# MainPower.net
KiCad netlist of a schematic drawn in EAGLE
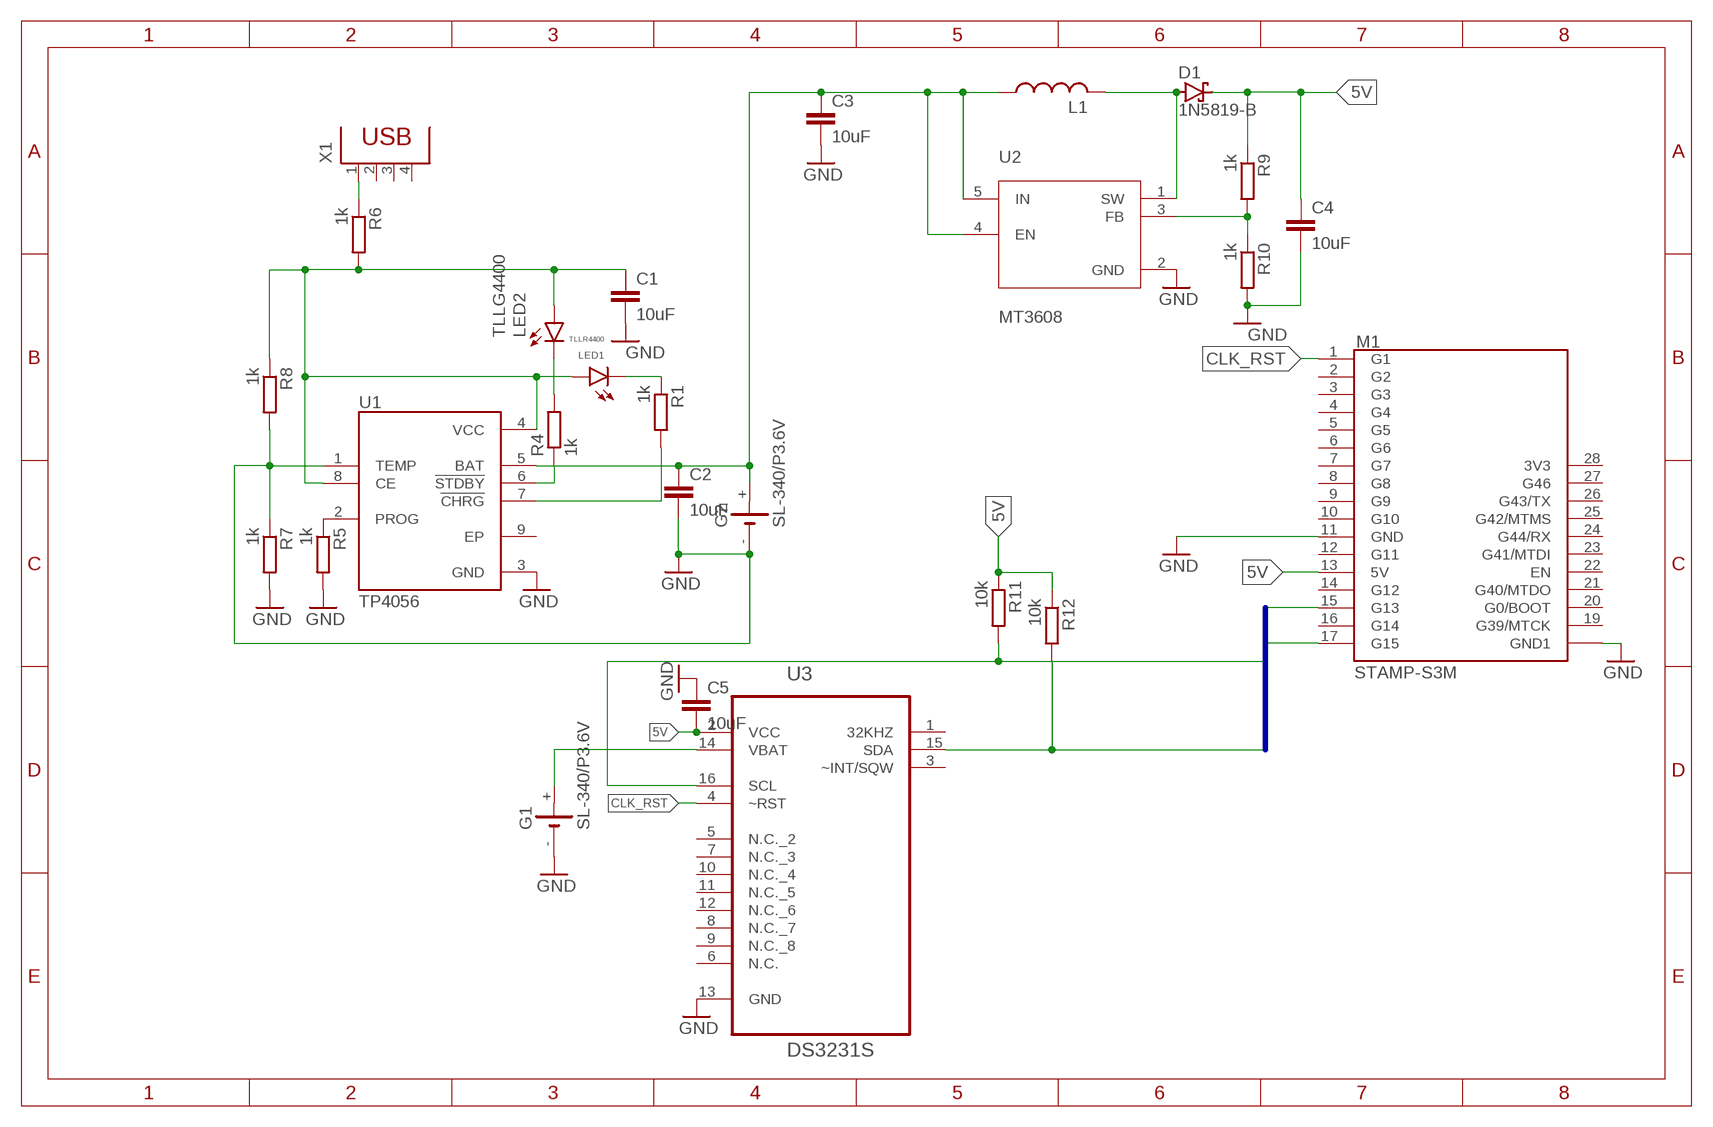
[diagram p0: schematic, sheet 1]

(export (version "E")
  (design (tool "Eeschema 10.0.6"))
  (components
    (comp (ref "C1")
      (value "10uF")
      (footprint "eagle-import:C2.5-3")
      (libsource (lib "eagle-import") (part "C2,5-3"))
    )
    (comp (ref "C2")
      (value "10uF")
      (footprint "eagle-import:C2.5-3")
      (libsource (lib "eagle-import") (part "C2,5-3"))
    )
    (comp (ref "C3")
      (value "10uF")
      (footprint "eagle-import:C2.5-3")
      (libsource (lib "eagle-import") (part "C2,5-3"))
    )
    (comp (ref "C4")
      (value "10uF")
      (footprint "eagle-import:C2.5-3")
      (libsource (lib "eagle-import") (part "C2,5-3"))
    )
    (comp (ref "C5")
      (value "10uF")
      (footprint "eagle-import:C2.5-3")
      (libsource (lib "eagle-import") (part "C2,5-3"))
    )
    (comp (ref "D1")
      (value "1N5819-B")
      (footprint "eagle-import:DO41-7.6")
      (libsource (lib "eagle-import") (part "1N5819-B"))
    )
    (comp (ref "G1")
      (value "SL-340/P3.6V")
      (footprint "eagle-import:SL-340_P3.6V")
      (libsource (lib "eagle-import") (part "SL-340/P3.6V"))
    )
    (comp (ref "G2")
      (value "SL-340/P3.6V")
      (footprint "eagle-import:SL-340_P3.6V")
      (libsource (lib "eagle-import") (part "SL-340/P3.6V"))
    )
    (comp (ref "L1")
      (value "L-US0204/7")
      (footprint "eagle-import:0204_7")
      (libsource (lib "eagle-import") (part "L-US0204/7"))
    )
    (comp (ref "LED1")
      (value "TLLR4400")
      (footprint "eagle-import:LED3MM")
      (fields (field (name "MF") "VISHAY SEMICONDUCTOR"))
      (libsource (lib "eagle-import") (part "TLLR4400"))
    )
    (comp (ref "LED2")
      (value "TLLG4400")
      (footprint "eagle-import:LED3MM")
      (fields (field (name "MF") "VISHAY SEMICONDUCTOR"))
      (libsource (lib "eagle-import") (part "TLLG4400"))
    )
    (comp (ref "R1")
      (value "1k")
      (footprint "eagle-import:0204V")
      (libsource (lib "eagle-import") (part "R-EU_0204/2V"))
    )
    (comp (ref "R4")
      (value "1k")
      (footprint "eagle-import:0204V")
      (libsource (lib "eagle-import") (part "R-EU_0204/2V"))
    )
    (comp (ref "R5")
      (value "1k")
      (footprint "eagle-import:0204V")
      (libsource (lib "eagle-import") (part "R-EU_0204/2V"))
    )
    (comp (ref "R6")
      (value "1k")
      (footprint "eagle-import:0204V")
      (libsource (lib "eagle-import") (part "R-EU_0204/2V"))
    )
    (comp (ref "R7")
      (value "1k")
      (footprint "eagle-import:0204V")
      (libsource (lib "eagle-import") (part "R-EU_0204/2V"))
    )
    (comp (ref "R8")
      (value "1k")
      (footprint "eagle-import:0204V")
      (libsource (lib "eagle-import") (part "R-EU_0204/2V"))
    )
    (comp (ref "R9")
      (value "1k")
      (footprint "eagle-import:0204V")
      (libsource (lib "eagle-import") (part "R-EU_0204/2V"))
    )
    (comp (ref "R10")
      (value "1k")
      (footprint "eagle-import:0204V")
      (libsource (lib "eagle-import") (part "R-EU_0204/2V"))
    )
    (comp (ref "R11")
      (value "10k")
      (footprint "eagle-import:0204V")
      (libsource (lib "eagle-import") (part "R-EU_0204/2V"))
    )
    (comp (ref "R12")
      (value "10k")
      (footprint "eagle-import:0204V")
      (libsource (lib "eagle-import") (part "R-EU_0204/2V"))
    )
    (comp (ref "U$2")
      (value "STAMP-S3M-PIN")
      (footprint "eagle-import:STAMPS3_PIN_FTP")
      (libsource (lib "eagle-import") (part "STAMP-S3M-PIN"))
    )
    (comp (ref "U1")
      (value "TP4056")
      (footprint "eagle-import:SOP127P600X175-9N")
      (fields (field (name "MF") "NanJing Top Power ASIC Corp."))
      (libsource (lib "eagle-import") (part "TP4056"))
    )
    (comp (ref "U2")
      (value "MT3608")
      (footprint "eagle-import:SOT95P280X145-6N")
      (fields (field (name "MF") "Aerosemi Technology Co., Ltd"))
      (libsource (lib "eagle-import") (part "MT3608"))
    )
    (comp (ref "U3")
      (value "DS3231S")
      (footprint "eagle-import:SOIC127P1032X265-16N")
      (fields (field (name "MF") "Analog Devices") (field (name "MP") "DS3231S#"))
      (libsource (lib "eagle-import") (part "DS3231S"))
    )
    (comp (ref "X1")
      (value "PN61729")
      (footprint "eagle-import:PN61729")
      (libsource (lib "eagle-import") (part "PN61729"))
    )
  )
  (nets
    (net (code "1") (name "/3V3") (class "Default")
      (node (ref "U$2") (pin "28") (pinfunction "3V3_28") (pintype "power_in"))
    )
    (net (code "2") (name "/SCL") (class "Default")
      (node (ref "R11") (pin "2") (pinfunction "2_2") (pintype "passive"))
      (node (ref "U$2") (pin "17") (pinfunction "G15_17") (pintype "bidirectional"))
      (node (ref "U3") (pin "16") (pinfunction "SCL_16") (pintype "input"))
    )
    (net (code "3") (name "/SDA") (class "Default")
      (node (ref "R12") (pin "2") (pinfunction "2_2") (pintype "passive"))
      (node (ref "U$2") (pin "15") (pinfunction "G13_15") (pintype "bidirectional"))
      (node (ref "U3") (pin "15") (pinfunction "SDA_15") (pintype "bidirectional"))
    )
    (net (code "4") (name "/USB") (class "Default")
      (node (ref "C1") (pin "1") (pinfunction "1_1") (pintype "passive"))
      (node (ref "LED1") (pin "A") (pinfunction "A_A") (pintype "passive"))
      (node (ref "LED2") (pin "A") (pinfunction "A_A") (pintype "passive"))
      (node (ref "R6") (pin "1") (pinfunction "1_1") (pintype "passive"))
      (node (ref "R6") (pin "2") (pinfunction "2_2") (pintype "passive"))
      (node (ref "R8") (pin "1") (pinfunction "1_1") (pintype "passive"))
      (node (ref "U1") (pin "4") (pinfunction "VCC_4") (pintype "power_in"))
      (node (ref "U1") (pin "8") (pinfunction "CE_8") (pintype "input"))
      (node (ref "X1") (pin "1") (pinfunction "1_1") (pintype "passive"))
    )
    (net (code "5") (name "5V") (class "Default")
      (node (ref "C4") (pin "1") (pinfunction "1_1") (pintype "passive"))
      (node (ref "C5") (pin "2") (pinfunction "2_2") (pintype "passive"))
      (node (ref "D1") (pin "C") (pinfunction "C_C") (pintype "passive"))
      (node (ref "R11") (pin "1") (pinfunction "1_1") (pintype "passive"))
      (node (ref "R12") (pin "1") (pinfunction "1_1") (pintype "passive"))
      (node (ref "R9") (pin "1") (pinfunction "1_1") (pintype "passive"))
      (node (ref "U$2") (pin "13") (pinfunction "5V_13") (pintype "power_in"))
      (node (ref "U3") (pin "2") (pinfunction "VCC_2") (pintype "power_in"))
    )
    (net (code "6") (name "CLK_RST") (class "Default")
      (node (ref "U$2") (pin "1") (pinfunction "G1_1") (pintype "bidirectional"))
      (node (ref "U3") (pin "4") (pinfunction "~{RST}_4") (pintype "bidirectional"))
    )
    (net (code "7") (name "GND") (class "Default")
      (node (ref "C1") (pin "2") (pinfunction "2_2") (pintype "passive"))
      (node (ref "C2") (pin "2") (pinfunction "2_2") (pintype "passive"))
      (node (ref "C3") (pin "2") (pinfunction "2_2") (pintype "passive"))
      (node (ref "C4") (pin "2") (pinfunction "2_2") (pintype "passive"))
      (node (ref "C5") (pin "1") (pinfunction "1_1") (pintype "passive"))
      (node (ref "G1") (pin "-") (pinfunction "-_-") (pintype "passive"))
      (node (ref "G2") (pin "-") (pinfunction "-_-") (pintype "passive"))
      (node (ref "R10") (pin "2") (pinfunction "2_2") (pintype "passive"))
      (node (ref "R5") (pin "2") (pinfunction "2_2") (pintype "passive"))
      (node (ref "R7") (pin "1") (pinfunction "1_1") (pintype "passive"))
      (node (ref "R7") (pin "2") (pinfunction "2_2") (pintype "passive"))
      (node (ref "R8") (pin "2") (pinfunction "2_2") (pintype "passive"))
      (node (ref "U$2") (pin "11") (pinfunction "GND_11") (pintype "power_in"))
      (node (ref "U$2") (pin "18") (pinfunction "GND1_18") (pintype "power_in"))
      (node (ref "U1") (pin "1") (pinfunction "TEMP_1") (pintype "input"))
      (node (ref "U1") (pin "3") (pinfunction "GND_3") (pintype "power_in"))
      (node (ref "U2") (pin "2") (pinfunction "GND_2") (pintype "power_in"))
      (node (ref "U3") (pin "13") (pinfunction "GND_13") (pintype "passive"))
    )
    (net (code "8") (name "Net-(LED1-C)") (class "Default")
      (node (ref "LED1") (pin "K") (pinfunction "C_K") (pintype "passive"))
      (node (ref "R1") (pin "1") (pinfunction "1_1") (pintype "passive"))
    )
    (net (code "9") (name "Net-(LED2-C)") (class "Default")
      (node (ref "LED2") (pin "K") (pinfunction "C_K") (pintype "passive"))
      (node (ref "R4") (pin "2") (pinfunction "2_2") (pintype "passive"))
    )
    (net (code "10") (name "Net-(U1-BAT)") (class "Default")
      (node (ref "C2") (pin "1") (pinfunction "1_1") (pintype "passive"))
      (node (ref "C3") (pin "1") (pinfunction "1_1") (pintype "passive"))
      (node (ref "G2") (pin "+") (pinfunction "+_+") (pintype "passive"))
      (node (ref "L1") (pin "1") (pinfunction "1_1") (pintype "passive"))
      (node (ref "U1") (pin "5") (pinfunction "BAT_5") (pintype "output"))
      (node (ref "U2") (pin "4") (pinfunction "EN_4") (pintype "input"))
      (node (ref "U2") (pin "5") (pinfunction "IN_5") (pintype "input"))
    )
    (net (code "11") (name "Net-(U1-PROG)") (class "Default")
      (node (ref "R5") (pin "1") (pinfunction "1_1") (pintype "passive"))
      (node (ref "U1") (pin "2") (pinfunction "PROG_2") (pintype "bidirectional"))
    )
    (net (code "12") (name "Net-(U1-~{CHRG})") (class "Default")
      (node (ref "R1") (pin "2") (pinfunction "2_2") (pintype "passive"))
      (node (ref "U1") (pin "7") (pinfunction "~{CHRG}_7") (pintype "output"))
    )
    (net (code "13") (name "Net-(U1-~{STDBY})") (class "Default")
      (node (ref "R4") (pin "1") (pinfunction "1_1") (pintype "passive"))
      (node (ref "U1") (pin "6") (pinfunction "~{STDBY}_6") (pintype "output"))
    )
    (net (code "14") (name "Net-(U2-FB)") (class "Default")
      (node (ref "R10") (pin "1") (pinfunction "1_1") (pintype "passive"))
      (node (ref "R9") (pin "2") (pinfunction "2_2") (pintype "passive"))
      (node (ref "U2") (pin "3") (pinfunction "FB_3") (pintype "input"))
    )
    (net (code "15") (name "Net-(U2-SW)") (class "Default")
      (node (ref "D1") (pin "A") (pinfunction "A_A") (pintype "passive"))
      (node (ref "L1") (pin "2") (pinfunction "2_2") (pintype "passive"))
      (node (ref "U2") (pin "1") (pinfunction "SW_1") (pintype "output"))
    )
    (net (code "16") (name "Net-(U3-VBAT)") (class "Default")
      (node (ref "G1") (pin "+") (pinfunction "+_+") (pintype "passive"))
      (node (ref "U3") (pin "14") (pinfunction "VBAT_14") (pintype "power_in"))
    )
    (net (code "17") (name "unconnected-(U$2-EN-Pad22)") (class "Default")
      (node (ref "U$2") (pin "22") (pinfunction "EN_22") (pintype "input"))
    )
    (net (code "18") (name "unconnected-(U$2-G0{slash}BOOT-Pad20)") (class "Default")
      (node (ref "U$2") (pin "20") (pinfunction "G0/BOOT_20") (pintype "bidirectional"))
    )
    (net (code "19") (name "unconnected-(U$2-G2-Pad2)") (class "Default")
      (node (ref "U$2") (pin "2") (pinfunction "G2_2") (pintype "bidirectional"))
    )
    (net (code "20") (name "unconnected-(U$2-G3-Pad3)") (class "Default")
      (node (ref "U$2") (pin "3") (pinfunction "G3_3") (pintype "bidirectional"))
    )
    (net (code "21") (name "unconnected-(U$2-G4-Pad4)") (class "Default")
      (node (ref "U$2") (pin "4") (pinfunction "G4_4") (pintype "bidirectional"))
    )
    (net (code "22") (name "unconnected-(U$2-G5-Pad5)") (class "Default")
      (node (ref "U$2") (pin "5") (pinfunction "G5_5") (pintype "bidirectional"))
    )
    (net (code "23") (name "unconnected-(U$2-G6-Pad6)") (class "Default")
      (node (ref "U$2") (pin "6") (pinfunction "G6_6") (pintype "bidirectional"))
    )
    (net (code "24") (name "unconnected-(U$2-G7-Pad7)") (class "Default")
      (node (ref "U$2") (pin "7") (pinfunction "G7_7") (pintype "bidirectional"))
    )
    (net (code "25") (name "unconnected-(U$2-G8-Pad8)") (class "Default")
      (node (ref "U$2") (pin "8") (pinfunction "G8_8") (pintype "bidirectional"))
    )
    (net (code "26") (name "unconnected-(U$2-G9-Pad9)") (class "Default")
      (node (ref "U$2") (pin "9") (pinfunction "G9_9") (pintype "bidirectional"))
    )
    (net (code "27") (name "unconnected-(U$2-G10-Pad10)") (class "Default")
      (node (ref "U$2") (pin "10") (pinfunction "G10_10") (pintype "bidirectional"))
    )
    (net (code "28") (name "unconnected-(U$2-G11-Pad12)") (class "Default")
      (node (ref "U$2") (pin "12") (pinfunction "G11_12") (pintype "bidirectional"))
    )
    (net (code "29") (name "unconnected-(U$2-G12-Pad14)") (class "Default")
      (node (ref "U$2") (pin "14") (pinfunction "G12_14") (pintype "bidirectional"))
    )
    (net (code "30") (name "unconnected-(U$2-G14-Pad16)") (class "Default")
      (node (ref "U$2") (pin "16") (pinfunction "G14_16") (pintype "bidirectional"))
    )
    (net (code "31") (name "unconnected-(U$2-G39{slash}MTCK-Pad19)") (class "Default")
      (node (ref "U$2") (pin "19") (pinfunction "G39/MTCK_19") (pintype "bidirectional"))
    )
    (net (code "32") (name "unconnected-(U$2-G40{slash}MTDO-Pad21)") (class "Default")
      (node (ref "U$2") (pin "21") (pinfunction "G40/MTDO_21") (pintype "bidirectional"))
    )
    (net (code "33") (name "unconnected-(U$2-G41{slash}MTDI-Pad23)") (class "Default")
      (node (ref "U$2") (pin "23") (pinfunction "G41/MTDI_23") (pintype "bidirectional"))
    )
    (net (code "34") (name "unconnected-(U$2-G42{slash}MTMS-Pad25)") (class "Default")
      (node (ref "U$2") (pin "25") (pinfunction "G42/MTMS_25") (pintype "bidirectional"))
    )
    (net (code "35") (name "unconnected-(U$2-G43{slash}TX-Pad26)") (class "Default")
      (node (ref "U$2") (pin "26") (pinfunction "G43/TX_26") (pintype "output"))
    )
    (net (code "36") (name "unconnected-(U$2-G44{slash}RX-Pad24)") (class "Default")
      (node (ref "U$2") (pin "24") (pinfunction "G44/RX_24") (pintype "input"))
    )
    (net (code "37") (name "unconnected-(U$2-G46-Pad27)") (class "Default")
      (node (ref "U$2") (pin "27") (pinfunction "G46_27") (pintype "bidirectional"))
    )
    (net (code "38") (name "unconnected-(U1-EP-Pad9)") (class "Default")
      (node (ref "U1") (pin "9") (pinfunction "EP_9") (pintype "passive"))
    )
    (net (code "39") (name "unconnected-(U3-32KHZ-Pad1)") (class "Default")
      (node (ref "U3") (pin "1") (pinfunction "32KHZ_1") (pintype "output"))
    )
    (net (code "40") (name "unconnected-(U3-N.C.-Pad6)") (class "Default")
      (node (ref "U3") (pin "6") (pinfunction "N.C._6") (pintype "no_connect"))
    )
    (net (code "41") (name "unconnected-(U3-N.C._2-Pad5)") (class "Default")
      (node (ref "U3") (pin "5") (pinfunction "N.C._2_5") (pintype "no_connect"))
    )
    (net (code "42") (name "unconnected-(U3-N.C._3-Pad7)") (class "Default")
      (node (ref "U3") (pin "7") (pinfunction "N.C._3_7") (pintype "no_connect"))
    )
    (net (code "43") (name "unconnected-(U3-N.C._4-Pad10)") (class "Default")
      (node (ref "U3") (pin "10") (pinfunction "N.C._4_10") (pintype "no_connect"))
    )
    (net (code "44") (name "unconnected-(U3-N.C._5-Pad11)") (class "Default")
      (node (ref "U3") (pin "11") (pinfunction "N.C._5_11") (pintype "no_connect"))
    )
    (net (code "45") (name "unconnected-(U3-N.C._6-Pad12)") (class "Default")
      (node (ref "U3") (pin "12") (pinfunction "N.C._6_12") (pintype "no_connect"))
    )
    (net (code "46") (name "unconnected-(U3-N.C._7-Pad8)") (class "Default")
      (node (ref "U3") (pin "8") (pinfunction "N.C._7_8") (pintype "no_connect"))
    )
    (net (code "47") (name "unconnected-(U3-N.C._8-Pad9)") (class "Default")
      (node (ref "U3") (pin "9") (pinfunction "N.C._8_9") (pintype "no_connect"))
    )
    (net (code "48") (name "unconnected-(U3-~{INT{slash}SQW}-Pad3)") (class "Default")
      (node (ref "U3") (pin "3") (pinfunction "~{INT/SQW}_3") (pintype "output"))
    )
    (net (code "49") (name "unconnected-(X1-Pad2)") (class "Default")
      (node (ref "X1") (pin "2") (pinfunction "2_2") (pintype "passive"))
    )
    (net (code "50") (name "unconnected-(X1-Pad3)") (class "Default")
      (node (ref "X1") (pin "3") (pinfunction "3_3") (pintype "passive"))
    )
    (net (code "51") (name "unconnected-(X1-Pad4)") (class "Default")
      (node (ref "X1") (pin "4") (pinfunction "4_4") (pintype "passive"))
    )
  )
)
